# Arm_controller.net
KiCad netlist of a schematic drawn in EAGLE
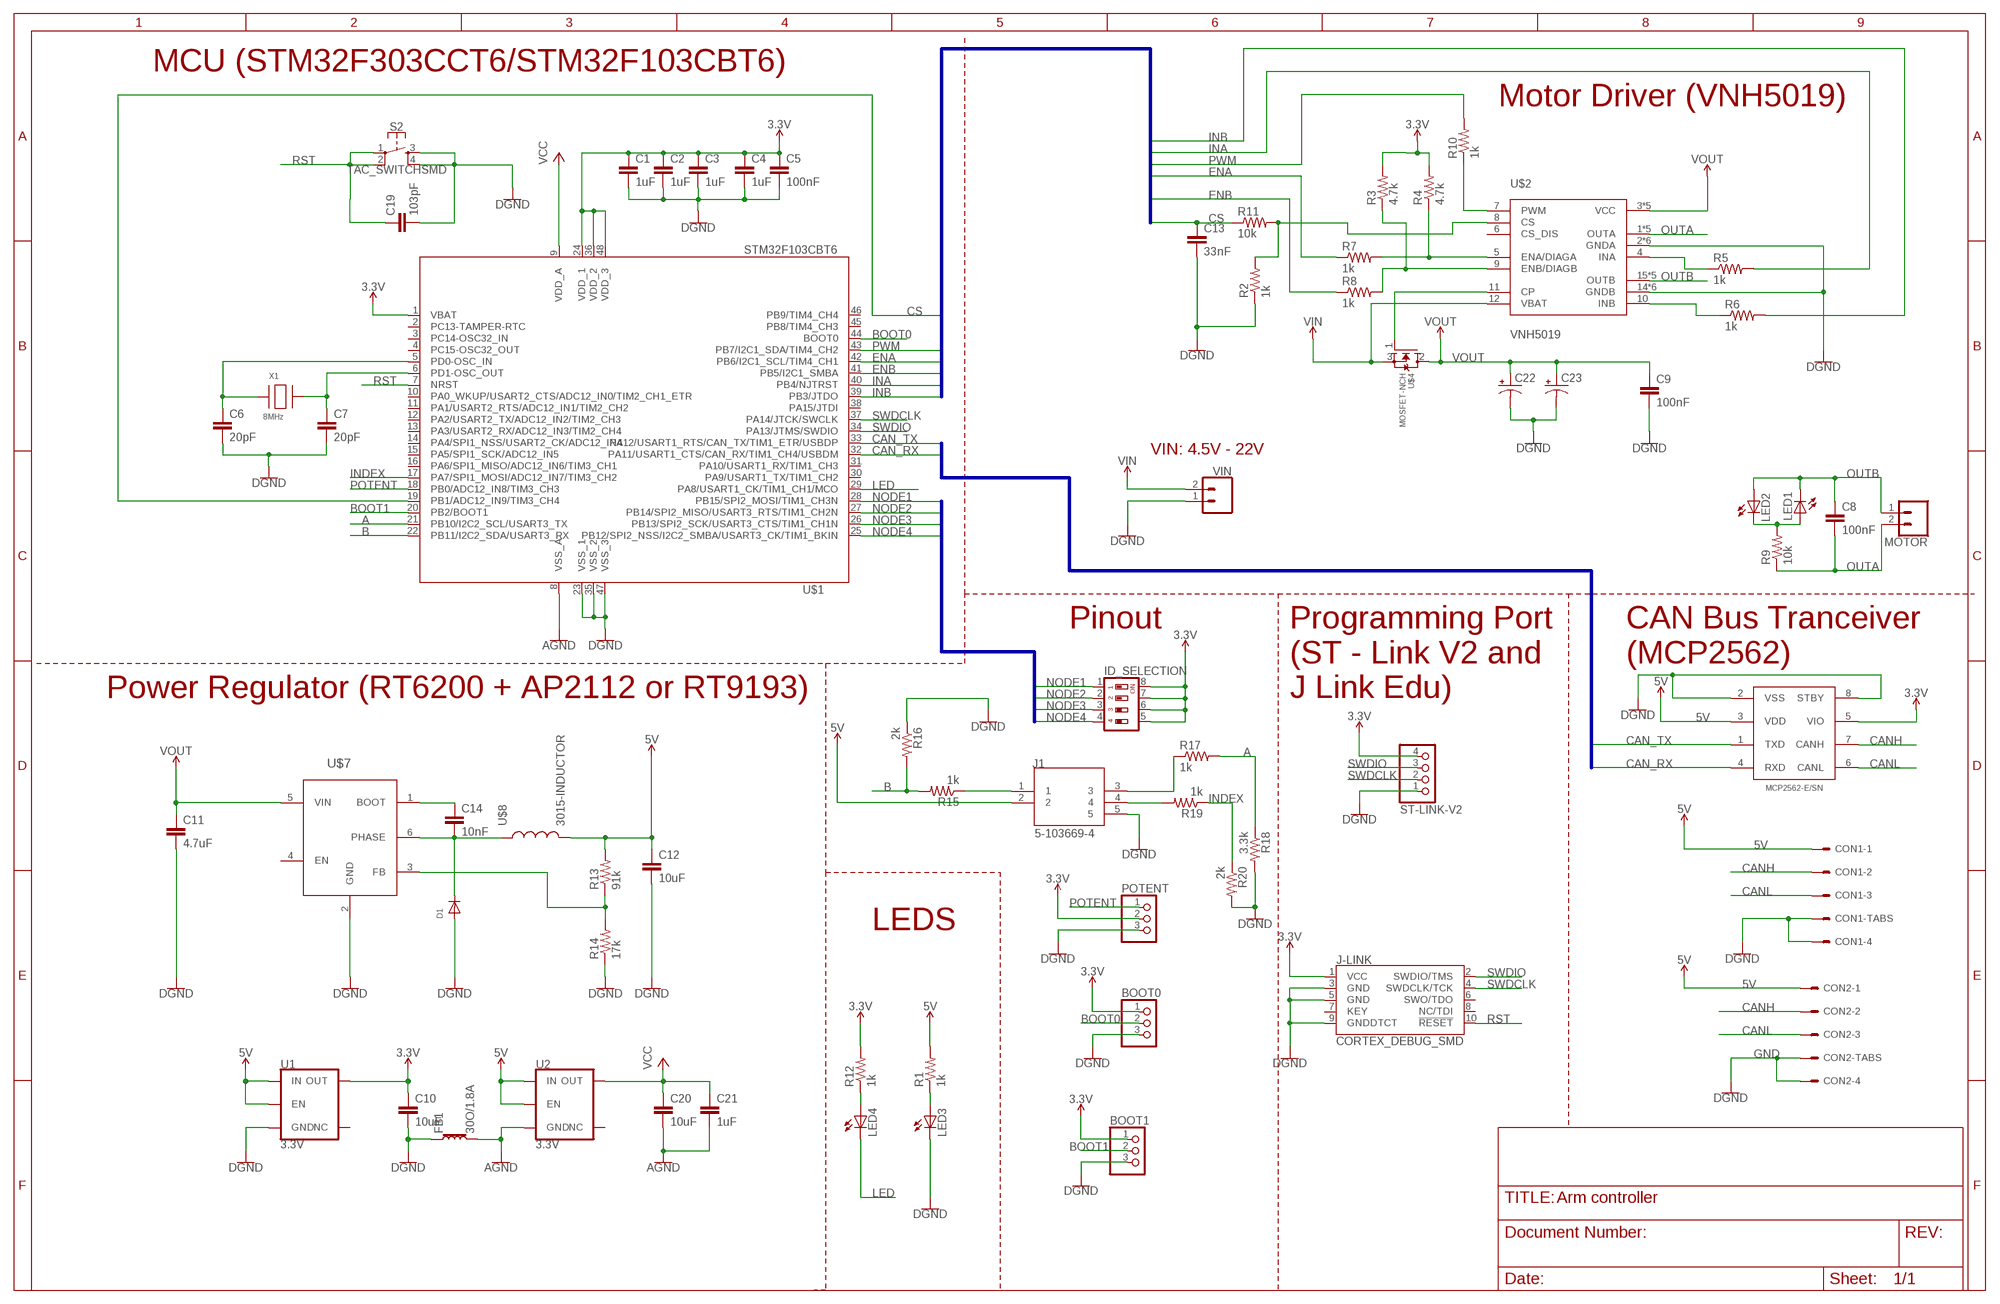
[diagram p0: schematic, sheet 1]

(export (version "E")
  (design (tool "Eeschema 10.0.6"))
  (components
    (comp (ref "BOOT0")
      (value "PINHD-1X3")
      (footprint "eagle-import:1X03")
      (libsource (lib "eagle-import") (part "PINHD-1X3"))
    )
    (comp (ref "BOOT1")
      (value "PINHD-1X3")
      (footprint "eagle-import:1X03")
      (libsource (lib "eagle-import") (part "PINHD-1X3"))
    )
    (comp (ref "C1")
      (value "1uF")
      (footprint "eagle-import:C0805")
      (libsource (lib "eagle-import") (part "C-EUC0805"))
    )
    (comp (ref "C2")
      (value "1uF")
      (footprint "eagle-import:C0805")
      (libsource (lib "eagle-import") (part "C-EUC0805"))
    )
    (comp (ref "C3")
      (value "1uF")
      (footprint "eagle-import:C0805")
      (libsource (lib "eagle-import") (part "C-EUC0805"))
    )
    (comp (ref "C4")
      (value "1uF")
      (footprint "eagle-import:C0805")
      (libsource (lib "eagle-import") (part "C-EUC0805"))
    )
    (comp (ref "C5")
      (value "100nF")
      (footprint "eagle-import:C0805")
      (libsource (lib "eagle-import") (part "C-EUC0805"))
    )
    (comp (ref "C6")
      (value "20pF")
      (footprint "eagle-import:C0805")
      (libsource (lib "eagle-import") (part "C-EUC0805"))
    )
    (comp (ref "C7")
      (value "20pF")
      (footprint "eagle-import:C0805")
      (libsource (lib "eagle-import") (part "C-EUC0805"))
    )
    (comp (ref "C8")
      (value "100nF")
      (footprint "eagle-import:C1206")
      (libsource (lib "eagle-import") (part "resistor_348_C-EUC1206"))
    )
    (comp (ref "C9")
      (value "100nF")
      (footprint "eagle-import:C0805")
      (libsource (lib "eagle-import") (part "C-EUC0805"))
    )
    (comp (ref "C10")
      (value "10uF")
      (footprint "eagle-import:C1206")
      (libsource (lib "eagle-import") (part "resistor_348_C-EUC1206"))
    )
    (comp (ref "C11")
      (value "4.7uF")
      (footprint "eagle-import:C0805")
      (libsource (lib "eagle-import") (part "C-EUC0805"))
    )
    (comp (ref "C12")
      (value "10uF")
      (footprint "eagle-import:C0805")
      (libsource (lib "eagle-import") (part "C-EUC0805"))
    )
    (comp (ref "C13")
      (value "33nF")
      (footprint "eagle-import:C0805")
      (libsource (lib "eagle-import") (part "C-EUC0805"))
    )
    (comp (ref "C14")
      (value "10nF")
      (footprint "eagle-import:C0805")
      (libsource (lib "eagle-import") (part "C-EUC0805"))
    )
    (comp (ref "C19")
      (value "103pF")
      (footprint "eagle-import:C0805")
      (libsource (lib "eagle-import") (part "C-EUC0805"))
    )
    (comp (ref "C20")
      (value "10uF")
      (footprint "eagle-import:C1206")
      (libsource (lib "eagle-import") (part "resistor_348_C-EUC1206"))
    )
    (comp (ref "C21")
      (value "1uF")
      (footprint "eagle-import:C0805")
      (libsource (lib "eagle-import") (part "C-EUC0805"))
    )
    (comp (ref "C22")
      (value "CPOL-USCT7343")
      (footprint "eagle-import:CT7343")
      (libsource (lib "eagle-import") (part "CPOL-USCT7343"))
    )
    (comp (ref "C23")
      (value "CPOL-USCT7343")
      (footprint "eagle-import:CT7343")
      (libsource (lib "eagle-import") (part "CPOL-USCT7343"))
    )
    (comp (ref "CON1")
      (value "SM04B-GHS-TB")
      (footprint "eagle-import:SM04B-GHS-TB")
      (libsource (lib "eagle-import") (part "SM04B-GHS-TB"))
    )
    (comp (ref "CON2")
      (value "SM04B-GHS-TB")
      (footprint "eagle-import:SM04B-GHS-TB")
      (libsource (lib "eagle-import") (part "SM04B-GHS-TB"))
    )
    (comp (ref "D1")
      (value "DIODESOD-123")
      (footprint "eagle-import:SOD-123")
      (libsource (lib "eagle-import") (part "DIODESOD-123"))
    )
    (comp (ref "FB1")
      (value "30O/1.8A")
      (footprint "eagle-import:0603")
      (libsource (lib "eagle-import") (part "FERRITE_BEAD-0603"))
    )
    (comp (ref "ID_SELECTION")
      (value "SMS-004")
      (footprint "eagle-import:SMS-004")
      (libsource (lib "eagle-import") (part "SMS-004"))
    )
    (comp (ref "J-LINK")
      (value "CORTEX_DEBUG_SMD")
      (footprint "eagle-import:SAMTECH_FTSH-105-01")
      (libsource (lib "eagle-import") (part "CORTEX_DEBUG_SMD"))
    )
    (comp (ref "J1")
      (value "5-103669-4")
      (footprint "eagle-import:TE_5-103669-4")
      (fields (field (name "MF") "TE Connectivity"))
      (libsource (lib "eagle-import") (part "5-103669-4"))
    )
    (comp (ref "LED1")
      (value "LEDCHIPLED_0805")
      (footprint "eagle-import:CHIPLED_0805")
      (libsource (lib "eagle-import") (part "LEDCHIPLED_0805"))
    )
    (comp (ref "LED2")
      (value "LEDCHIPLED_0805")
      (footprint "eagle-import:CHIPLED_0805")
      (libsource (lib "eagle-import") (part "LEDCHIPLED_0805"))
    )
    (comp (ref "LED3")
      (value "LEDCHIPLED_0805")
      (footprint "eagle-import:CHIPLED_0805")
      (libsource (lib "eagle-import") (part "LEDCHIPLED_0805"))
    )
    (comp (ref "LED4")
      (value "LEDCHIPLED_0805")
      (footprint "eagle-import:CHIPLED_0805")
      (libsource (lib "eagle-import") (part "LEDCHIPLED_0805"))
    )
    (comp (ref "MOTOR")
      (value "CONN_025MM")
      (footprint "eagle-import:SCREWTERMINAL-5MM-2")
      (libsource (lib "eagle-import") (part "CONN_025MM"))
    )
    (comp (ref "POTENT")
      (value "PINHD-1X3")
      (footprint "eagle-import:1X03")
      (libsource (lib "eagle-import") (part "PINHD-1X3"))
    )
    (comp (ref "R1")
      (value "1k")
      (footprint "eagle-import:R0805")
      (libsource (lib "eagle-import") (part "R-US_R0805"))
    )
    (comp (ref "R2")
      (value "1k")
      (footprint "eagle-import:R0805")
      (libsource (lib "eagle-import") (part "R-US_R0805"))
    )
    (comp (ref "R3")
      (value "4.7k")
      (footprint "eagle-import:R0805")
      (libsource (lib "eagle-import") (part "R-US_R0805"))
    )
    (comp (ref "R4")
      (value "4.7k")
      (footprint "eagle-import:R0805")
      (libsource (lib "eagle-import") (part "R-US_R0805"))
    )
    (comp (ref "R5")
      (value "1k")
      (footprint "eagle-import:R0805")
      (libsource (lib "eagle-import") (part "R-US_R0805"))
    )
    (comp (ref "R6")
      (value "1k")
      (footprint "eagle-import:R0805")
      (libsource (lib "eagle-import") (part "R-US_R0805"))
    )
    (comp (ref "R7")
      (value "1k")
      (footprint "eagle-import:R0805")
      (libsource (lib "eagle-import") (part "R-US_R0805"))
    )
    (comp (ref "R8")
      (value "1k")
      (footprint "eagle-import:R0805")
      (libsource (lib "eagle-import") (part "R-US_R0805"))
    )
    (comp (ref "R9")
      (value "10k")
      (footprint "eagle-import:R0805")
      (libsource (lib "eagle-import") (part "R-US_R0805"))
    )
    (comp (ref "R10")
      (value "1k")
      (footprint "eagle-import:R0805")
      (libsource (lib "eagle-import") (part "R-US_R0805"))
    )
    (comp (ref "R11")
      (value "10k")
      (footprint "eagle-import:R0805")
      (libsource (lib "eagle-import") (part "R-US_R0805"))
    )
    (comp (ref "R12")
      (value "1k")
      (footprint "eagle-import:R0805")
      (libsource (lib "eagle-import") (part "R-US_R0805"))
    )
    (comp (ref "R13")
      (value "91k")
      (footprint "eagle-import:R0805")
      (libsource (lib "eagle-import") (part "R-US_R0805"))
    )
    (comp (ref "R14")
      (value "17k")
      (footprint "eagle-import:R0805")
      (libsource (lib "eagle-import") (part "R-US_R0805"))
    )
    (comp (ref "R15")
      (value "1k")
      (footprint "eagle-import:R0805")
      (libsource (lib "eagle-import") (part "R-US_R0805"))
    )
    (comp (ref "R16")
      (value "2k")
      (footprint "eagle-import:R0805")
      (libsource (lib "eagle-import") (part "R-US_R0805"))
    )
    (comp (ref "R17")
      (value "1k")
      (footprint "eagle-import:R0805")
      (libsource (lib "eagle-import") (part "R-US_R0805"))
    )
    (comp (ref "R18")
      (value "3.3k")
      (footprint "eagle-import:R0805")
      (libsource (lib "eagle-import") (part "R-US_R0805"))
    )
    (comp (ref "R19")
      (value "1k")
      (footprint "eagle-import:R0805")
      (libsource (lib "eagle-import") (part "R-US_R0805"))
    )
    (comp (ref "R20")
      (value "2k")
      (footprint "eagle-import:R0805")
      (libsource (lib "eagle-import") (part "R-US_R0805"))
    )
    (comp (ref "S2")
      (value "TAC_SWITCHSMD")
      (footprint "eagle-import:TACTILE_SWITCH_SMD_5.2MM")
      (libsource (lib "eagle-import") (part "MOMENTARY-SWITCH-SPST-2-SMD-5.2MM"))
    )
    (comp (ref "ST-LINK-V2")
      (value "PINHD-1X4")
      (footprint "eagle-import:1X04")
      (libsource (lib "eagle-import") (part "PINHD-1X4"))
    )
    (comp (ref "U$1")
      (value "STM32F103CBT6")
      (footprint "eagle-import:STM32_LQFP48")
      (libsource (lib "eagle-import") (part "STM32F103CBT6"))
    )
    (comp (ref "U$2")
      (value "VNH5019")
      (footprint "eagle-import:MULTIPOWERSO-30")
      (libsource (lib "eagle-import") (part "VNH5019"))
    )
    (comp (ref "U$3")
      (value "MCP2562-E/SN")
      (footprint "eagle-import:SOIC8")
      (libsource (lib "eagle-import") (part "MCP2562-E/SN"))
    )
    (comp (ref "U$4")
      (value "MOSFET-NCH")
      (footprint "eagle-import:TO252-3")
      (libsource (lib "eagle-import") (part "MOSFET-NCH"))
    )
    (comp (ref "U$7")
      (value "RT6200")
      (footprint "eagle-import:TSOT23-6")
      (libsource (lib "eagle-import") (part "RT6200"))
    )
    (comp (ref "U$8")
      (value "3015-INDUCTOR")
      (footprint "eagle-import:3015")
      (libsource (lib "eagle-import") (part "3015-INDUCTOR"))
    )
    (comp (ref "U1")
      (value "3.3V")
      (footprint "eagle-import:SOT23-5")
      (libsource (lib "eagle-import") (part "V_REG_AP2112K-3.3V"))
    )
    (comp (ref "U2")
      (value "3.3V")
      (footprint "eagle-import:SOT23-5")
      (libsource (lib "eagle-import") (part "V_REG_AP2112K-3.3V"))
    )
    (comp (ref "VIN")
      (value "CONN_025MM")
      (footprint "eagle-import:SCREWTERMINAL-5MM-2")
      (libsource (lib "eagle-import") (part "CONN_025MM"))
    )
    (comp (ref "X1")
      (value "8MHz")
      (footprint "eagle-import:NX5032")
      (libsource (lib "eagle-import") (part "XTALNX5032"))
    )
  )
  (nets
    (net (code "1") (name "/A") (class "Default")
      (node (ref "R17") (pin "2") (pinfunction "2_2") (pintype "passive"))
      (node (ref "R18") (pin "1") (pinfunction "1_1") (pintype "passive"))
      (node (ref "U$1") (pin "21") (pinfunction "PB10/I2C2_SCL/USART3_TX_21") (pintype "input"))
    )
    (net (code "2") (name "/B") (class "Default")
      (node (ref "R15") (pin "2") (pinfunction "2_2") (pintype "passive"))
      (node (ref "R16") (pin "2") (pinfunction "2_2") (pintype "passive"))
      (node (ref "U$1") (pin "22") (pinfunction "PB11/I2C2_SDA/USART3_RX_22") (pintype "input"))
    )
    (net (code "3") (name "/BOOT0") (class "Default")
      (node (ref "BOOT0") (pin "2") (pinfunction "2_2") (pintype "passive"))
      (node (ref "U$1") (pin "44") (pinfunction "BOOT0_44") (pintype "input"))
    )
    (net (code "4") (name "/BOOT1") (class "Default")
      (node (ref "BOOT1") (pin "2") (pinfunction "2_2") (pintype "passive"))
      (node (ref "U$1") (pin "20") (pinfunction "PB2/BOOT1_20") (pintype "bidirectional"))
    )
    (net (code "5") (name "/CANH") (class "Default")
      (node (ref "CON1") (pin "P$2") (pinfunction "S_P$2") (pintype "passive"))
      (node (ref "CON2") (pin "P$2") (pinfunction "S_P$2") (pintype "passive"))
      (node (ref "U$3") (pin "7") (pinfunction "CANH_7") (pintype "bidirectional"))
    )
    (net (code "6") (name "/CANL") (class "Default")
      (node (ref "CON1") (pin "P$3") (pinfunction "S_P$3") (pintype "passive"))
      (node (ref "CON2") (pin "P$3") (pinfunction "S_P$3") (pintype "passive"))
      (node (ref "U$3") (pin "6") (pinfunction "CANL_6") (pintype "bidirectional"))
    )
    (net (code "7") (name "/CAN_RX") (class "Default")
      (node (ref "U$1") (pin "32") (pinfunction "PA11/USART1_CTS/CAN_RX/TIM1_CH4/USBDM_32") (pintype "bidirectional"))
      (node (ref "U$3") (pin "4") (pinfunction "RXD_4") (pintype "bidirectional"))
    )
    (net (code "8") (name "/CAN_TX") (class "Default")
      (node (ref "U$1") (pin "33") (pinfunction "PA12/USART1_RTS/CAN_TX/TIM1_ETR/USBDP_33") (pintype "bidirectional"))
      (node (ref "U$3") (pin "1") (pinfunction "TXD_1") (pintype "bidirectional"))
    )
    (net (code "9") (name "/CS") (class "Default")
      (node (ref "C13") (pin "1") (pinfunction "1_1") (pintype "passive"))
      (node (ref "R11") (pin "1") (pinfunction "1_1") (pintype "passive"))
      (node (ref "U$1") (pin "19") (pinfunction "PB1/ADC12_IN9/TIM3_CH4_19") (pintype "bidirectional"))
    )
    (net (code "10") (name "/ENA") (class "Default")
      (node (ref "R7") (pin "1") (pinfunction "1_1") (pintype "passive"))
      (node (ref "U$1") (pin "42") (pinfunction "PB6/I2C1_SCL/TIM4_CH1_42") (pintype "input"))
    )
    (net (code "11") (name "/ENB") (class "Default")
      (node (ref "R8") (pin "1") (pinfunction "1_1") (pintype "passive"))
      (node (ref "U$1") (pin "41") (pinfunction "PB5/I2C1_SMBA_41") (pintype "input"))
    )
    (net (code "12") (name "/INA") (class "Default")
      (node (ref "R5") (pin "2") (pinfunction "2_2") (pintype "passive"))
      (node (ref "U$1") (pin "40") (pinfunction "PB4/NJTRST_40") (pintype "bidirectional"))
    )
    (net (code "13") (name "/INB") (class "Default")
      (node (ref "R6") (pin "2") (pinfunction "2_2") (pintype "passive"))
      (node (ref "U$1") (pin "39") (pinfunction "PB3/JTDO_39") (pintype "bidirectional"))
    )
    (net (code "14") (name "/INDEX") (class "Default")
      (node (ref "R19") (pin "1") (pinfunction "1_1") (pintype "passive"))
      (node (ref "R20") (pin "1") (pinfunction "1_1") (pintype "passive"))
      (node (ref "U$1") (pin "17") (pinfunction "PA7/SPI1_MOSI/ADC12_IN7/TIM3_CH2_17") (pintype "bidirectional"))
    )
    (net (code "15") (name "/LED") (class "Default")
      (node (ref "LED4") (pin "C") (pinfunction "C_C") (pintype "passive"))
      (node (ref "U$1") (pin "29") (pinfunction "PA8/USART1_CK/TIM1_CH1/MCO_29") (pintype "bidirectional"))
    )
    (net (code "16") (name "/NODE1") (class "Default")
      (node (ref "ID_SELECTION") (pin "1") (pinfunction "1_1") (pintype "passive"))
      (node (ref "U$1") (pin "28") (pinfunction "PB15/SPI2_MOSI/TIM1_CH3N_28") (pintype "input"))
    )
    (net (code "17") (name "/NODE2") (class "Default")
      (node (ref "ID_SELECTION") (pin "2") (pinfunction "2_2") (pintype "passive"))
      (node (ref "U$1") (pin "27") (pinfunction "PB14/SPI2_MISO/USART3_RTS/TIM1_CH2N_27") (pintype "input"))
    )
    (net (code "18") (name "/NODE3") (class "Default")
      (node (ref "ID_SELECTION") (pin "3") (pinfunction "3_3") (pintype "passive"))
      (node (ref "U$1") (pin "26") (pinfunction "PB13/SPI2_SCK/USART3_CTS/TIM1_CH1N_26") (pintype "input"))
    )
    (net (code "19") (name "/NODE4") (class "Default")
      (node (ref "ID_SELECTION") (pin "4") (pinfunction "4_4") (pintype "passive"))
      (node (ref "U$1") (pin "25") (pinfunction "PB12/SPI2_NSS/I2C2_SMBA/USART3_CK/TIM1_BKIN_25") (pintype "input"))
    )
    (net (code "20") (name "/OUTA") (class "Default")
      (node (ref "C8") (pin "2") (pinfunction "2_2") (pintype "passive"))
      (node (ref "MOTOR") (pin "2") (pinfunction "2_2") (pintype "passive"))
      (node (ref "R9") (pin "1") (pinfunction "1_1") (pintype "passive"))
      (node (ref "U$2") (pin "1") (pinfunction "OUTA_1") (pintype "bidirectional"))
      (node (ref "U$2") (pin "25") (pinfunction "OUTA_25") (pintype "bidirectional"))
      (node (ref "U$2") (pin "30") (pinfunction "OUTA_30") (pintype "bidirectional"))
      (node (ref "U$2") (pin "OUTA") (pinfunction "OUTA_OUTA") (pintype "bidirectional"))
      (node (ref "U$2") (pin "OUTA@1") (pinfunction "OUTA_OUTA@1") (pintype "bidirectional"))
    )
    (net (code "21") (name "/OUTB") (class "Default")
      (node (ref "C8") (pin "1") (pinfunction "1_1") (pintype "passive"))
      (node (ref "LED1") (pin "C") (pinfunction "C_C") (pintype "passive"))
      (node (ref "LED2") (pin "A") (pinfunction "A_A") (pintype "passive"))
      (node (ref "MOTOR") (pin "1") (pinfunction "1_1") (pintype "passive"))
      (node (ref "U$2") (pin "15") (pinfunction "OUTB_15") (pintype "bidirectional"))
      (node (ref "U$2") (pin "16") (pinfunction "OUTB_16") (pintype "bidirectional"))
      (node (ref "U$2") (pin "21") (pinfunction "OUTB_21") (pintype "bidirectional"))
      (node (ref "U$2") (pin "OUTB") (pinfunction "OUTB_OUTB") (pintype "bidirectional"))
      (node (ref "U$2") (pin "OUTB@1") (pinfunction "OUTB_OUTB@1") (pintype "bidirectional"))
    )
    (net (code "22") (name "/POTENT") (class "Default")
      (node (ref "POTENT") (pin "1") (pinfunction "1_1") (pintype "passive"))
      (node (ref "U$1") (pin "18") (pinfunction "PB0/ADC12_IN8/TIM3_CH3_18") (pintype "bidirectional"))
    )
    (net (code "23") (name "/PWM") (class "Default")
      (node (ref "R10") (pin "2") (pinfunction "2_2") (pintype "passive"))
      (node (ref "U$1") (pin "43") (pinfunction "PB7/I2C1_SDA/TIM4_CH2_43") (pintype "bidirectional"))
    )
    (net (code "24") (name "/RST") (class "Default")
      (node (ref "C19") (pin "1") (pinfunction "1_1") (pintype "passive"))
      (node (ref "J-LINK") (pin "10") (pinfunction "~{RESET}_10") (pintype "bidirectional"))
      (node (ref "S2") (pin "1") (pinfunction "1_1") (pintype "passive"))
      (node (ref "S2") (pin "2") (pinfunction "2_2") (pintype "passive"))
      (node (ref "U$1") (pin "7") (pinfunction "NRST_7") (pintype "input"))
    )
    (net (code "25") (name "/SWDCLK") (class "Default")
      (node (ref "J-LINK") (pin "4") (pinfunction "SWDCLK/TCK_4") (pintype "bidirectional"))
      (node (ref "ST-LINK-V2") (pin "2") (pinfunction "2_2") (pintype "passive"))
      (node (ref "U$1") (pin "37") (pinfunction "PA14/JTCK/SWCLK_37") (pintype "bidirectional"))
    )
    (net (code "26") (name "/SWDIO") (class "Default")
      (node (ref "J-LINK") (pin "2") (pinfunction "SWDIO/TMS_2") (pintype "bidirectional"))
      (node (ref "ST-LINK-V2") (pin "3") (pinfunction "3_3") (pintype "passive"))
      (node (ref "U$1") (pin "34") (pinfunction "PA13/JTMS/SWDIO_34") (pintype "bidirectional"))
    )
    (net (code "27") (name "3.3V") (class "Default")
      (node (ref "BOOT0") (pin "1") (pinfunction "1_1") (pintype "passive"))
      (node (ref "BOOT1") (pin "1") (pinfunction "1_1") (pintype "passive"))
      (node (ref "C1") (pin "1") (pinfunction "1_1") (pintype "passive"))
      (node (ref "C10") (pin "1") (pinfunction "1_1") (pintype "passive"))
      (node (ref "C2") (pin "1") (pinfunction "1_1") (pintype "passive"))
      (node (ref "C3") (pin "1") (pinfunction "1_1") (pintype "passive"))
      (node (ref "C4") (pin "1") (pinfunction "1_1") (pintype "passive"))
      (node (ref "C5") (pin "1") (pinfunction "1_1") (pintype "passive"))
      (node (ref "ID_SELECTION") (pin "5") (pinfunction "5_5") (pintype "passive"))
      (node (ref "ID_SELECTION") (pin "6") (pinfunction "6_6") (pintype "passive"))
      (node (ref "ID_SELECTION") (pin "7") (pinfunction "7_7") (pintype "passive"))
      (node (ref "ID_SELECTION") (pin "8") (pinfunction "8_8") (pintype "passive"))
      (node (ref "J-LINK") (pin "1") (pinfunction "VCC_1") (pintype "bidirectional"))
      (node (ref "POTENT") (pin "2") (pinfunction "2_2") (pintype "passive"))
      (node (ref "R12") (pin "2") (pinfunction "2_2") (pintype "passive"))
      (node (ref "R3") (pin "2") (pinfunction "2_2") (pintype "passive"))
      (node (ref "R4") (pin "2") (pinfunction "2_2") (pintype "passive"))
      (node (ref "ST-LINK-V2") (pin "4") (pinfunction "4_4") (pintype "passive"))
      (node (ref "U$1") (pin "1") (pinfunction "VBAT_1") (pintype "power_in"))
      (node (ref "U$1") (pin "24") (pinfunction "VDD_1_24") (pintype "power_in"))
      (node (ref "U$1") (pin "36") (pinfunction "VDD_2_36") (pintype "power_in"))
      (node (ref "U$1") (pin "48") (pinfunction "VDD_3_48") (pintype "power_in"))
      (node (ref "U$3") (pin "5") (pinfunction "VIO_5") (pintype "bidirectional"))
      (node (ref "U1") (pin "5") (pinfunction "OUT_5") (pintype "passive"))
    )
    (net (code "28") (name "5V") (class "Default")
      (node (ref "C12") (pin "1") (pinfunction "1_1") (pintype "passive"))
      (node (ref "CON1") (pin "P$1") (pinfunction "S_P$1") (pintype "passive"))
      (node (ref "CON2") (pin "P$1") (pinfunction "S_P$1") (pintype "passive"))
      (node (ref "J1") (pin "2") (pinfunction "2_2") (pintype "passive"))
      (node (ref "R1") (pin "2") (pinfunction "2_2") (pintype "passive"))
      (node (ref "R13") (pin "2") (pinfunction "2_2") (pintype "passive"))
      (node (ref "U$3") (pin "3") (pinfunction "VDD_3") (pintype "bidirectional"))
      (node (ref "U$8") (pin "2") (pinfunction "2_2") (pintype "passive"))
      (node (ref "U1") (pin "1") (pinfunction "IN_1") (pintype "input"))
      (node (ref "U1") (pin "3") (pinfunction "EN_3") (pintype "input"))
      (node (ref "U2") (pin "1") (pinfunction "IN_1") (pintype "input"))
      (node (ref "U2") (pin "3") (pinfunction "EN_3") (pintype "input"))
    )
    (net (code "29") (name "AGND") (class "Default")
      (node (ref "C20") (pin "2") (pinfunction "2_2") (pintype "passive"))
      (node (ref "C21") (pin "2") (pinfunction "2_2") (pintype "passive"))
      (node (ref "FB1") (pin "2") (pinfunction "2_2") (pintype "passive"))
      (node (ref "U$1") (pin "8") (pinfunction "VSS_A_8") (pintype "power_in"))
      (node (ref "U2") (pin "2") (pinfunction "GND_2") (pintype "input"))
    )
    (net (code "30") (name "DGND") (class "Default")
      (node (ref "BOOT0") (pin "3") (pinfunction "3_3") (pintype "passive"))
      (node (ref "BOOT1") (pin "3") (pinfunction "3_3") (pintype "passive"))
      (node (ref "C1") (pin "2") (pinfunction "2_2") (pintype "passive"))
      (node (ref "C10") (pin "2") (pinfunction "2_2") (pintype "passive"))
      (node (ref "C11") (pin "2") (pinfunction "2_2") (pintype "passive"))
      (node (ref "C12") (pin "2") (pinfunction "2_2") (pintype "passive"))
      (node (ref "C13") (pin "2") (pinfunction "2_2") (pintype "passive"))
      (node (ref "C19") (pin "2") (pinfunction "2_2") (pintype "passive"))
      (node (ref "C2") (pin "2") (pinfunction "2_2") (pintype "passive"))
      (node (ref "C22") (pin "-") (pinfunction "-_-") (pintype "passive"))
      (node (ref "C23") (pin "-") (pinfunction "-_-") (pintype "passive"))
      (node (ref "C3") (pin "2") (pinfunction "2_2") (pintype "passive"))
      (node (ref "C4") (pin "2") (pinfunction "2_2") (pintype "passive"))
      (node (ref "C5") (pin "2") (pinfunction "2_2") (pintype "passive"))
      (node (ref "C6") (pin "2") (pinfunction "2_2") (pintype "passive"))
      (node (ref "C7") (pin "2") (pinfunction "2_2") (pintype "passive"))
      (node (ref "C9") (pin "2") (pinfunction "2_2") (pintype "passive"))
      (node (ref "CON1") (pin "P$4") (pinfunction "S_P$4") (pintype "passive"))
      (node (ref "CON1") (pin "P$5") (pinfunction "S_P$5") (pintype "passive"))
      (node (ref "CON1") (pin "P$6") (pinfunction "S_P$6") (pintype "passive"))
      (node (ref "CON2") (pin "P$4") (pinfunction "S_P$4") (pintype "passive"))
      (node (ref "CON2") (pin "P$5") (pinfunction "S_P$5") (pintype "passive"))
      (node (ref "CON2") (pin "P$6") (pinfunction "S_P$6") (pintype "passive"))
      (node (ref "D1") (pin "A") (pinfunction "A_A") (pintype "passive"))
      (node (ref "FB1") (pin "1") (pinfunction "1_1") (pintype "passive"))
      (node (ref "J-LINK") (pin "3") (pinfunction "GND_3") (pintype "bidirectional"))
      (node (ref "J-LINK") (pin "5") (pinfunction "GND_5") (pintype "bidirectional"))
      (node (ref "J-LINK") (pin "9") (pinfunction "GNDDTCT_9") (pintype "bidirectional"))
      (node (ref "J1") (pin "5") (pinfunction "5_5") (pintype "passive"))
      (node (ref "LED3") (pin "C") (pinfunction "C_C") (pintype "passive"))
      (node (ref "POTENT") (pin "3") (pinfunction "3_3") (pintype "passive"))
      (node (ref "R14") (pin "1") (pinfunction "1_1") (pintype "passive"))
      (node (ref "R16") (pin "1") (pinfunction "1_1") (pintype "passive"))
      (node (ref "R18") (pin "2") (pinfunction "2_2") (pintype "passive"))
      (node (ref "R2") (pin "1") (pinfunction "1_1") (pintype "passive"))
      (node (ref "R20") (pin "2") (pinfunction "2_2") (pintype "passive"))
      (node (ref "S2") (pin "3") (pinfunction "3_3") (pintype "passive"))
      (node (ref "S2") (pin "4") (pinfunction "4_4") (pintype "passive"))
      (node (ref "ST-LINK-V2") (pin "1") (pinfunction "1_1") (pintype "passive"))
      (node (ref "U$1") (pin "23") (pinfunction "VSS_1_23") (pintype "power_in"))
      (node (ref "U$1") (pin "35") (pinfunction "VSS_2_35") (pintype "power_in"))
      (node (ref "U$1") (pin "47") (pinfunction "VSS_3_47") (pintype "power_in"))
      (node (ref "U$2") (pin "14") (pinfunction "GNDB_14") (pintype "bidirectional"))
      (node (ref "U$2") (pin "17") (pinfunction "GNDB_17") (pintype "bidirectional"))
      (node (ref "U$2") (pin "18") (pinfunction "GNDB_18") (pintype "bidirectional"))
      (node (ref "U$2") (pin "19") (pinfunction "GNDB_19") (pintype "bidirectional"))
      (node (ref "U$2") (pin "2") (pinfunction "GNDA_2") (pintype "bidirectional"))
      (node (ref "U$2") (pin "20") (pinfunction "GNDB_20") (pintype "bidirectional"))
      (node (ref "U$2") (pin "22") (pinfunction "GNDA_22") (pintype "bidirectional"))
      (node (ref "U$2") (pin "24") (pinfunction "GNDB_24") (pintype "bidirectional"))
      (node (ref "U$2") (pin "26") (pinfunction "GNDA_26") (pintype "bidirectional"))
      (node (ref "U$2") (pin "27") (pinfunction "GNDA_27") (pintype "bidirectional"))
      (node (ref "U$2") (pin "28") (pinfunction "GNDA_28") (pintype "bidirectional"))
      (node (ref "U$2") (pin "29") (pinfunction "GNDA_29") (pintype "bidirectional"))
      (node (ref "U$3") (pin "2") (pinfunction "VSS_2") (pintype "bidirectional"))
      (node (ref "U$3") (pin "8") (pinfunction "STBY_8") (pintype "bidirectional"))
      (node (ref "U$7") (pin "2") (pinfunction "GND_2") (pintype "power_in"))
      (node (ref "U1") (pin "2") (pinfunction "GND_2") (pintype "input"))
      (node (ref "VIN") (pin "1") (pinfunction "1_1") (pintype "passive"))
    )
    (net (code "31") (name "Net-(J1-Pad1)") (class "Default")
      (node (ref "J1") (pin "1") (pinfunction "1_1") (pintype "passive"))
      (node (ref "R15") (pin "1") (pinfunction "1_1") (pintype "passive"))
    )
    (net (code "32") (name "Net-(J1-Pad3)") (class "Default")
      (node (ref "J1") (pin "3") (pinfunction "3_3") (pintype "passive"))
      (node (ref "R17") (pin "1") (pinfunction "1_1") (pintype "passive"))
    )
    (net (code "33") (name "Net-(J1-Pad4)") (class "Default")
      (node (ref "J1") (pin "4") (pinfunction "4_4") (pintype "passive"))
      (node (ref "R19") (pin "2") (pinfunction "2_2") (pintype "passive"))
    )
    (net (code "34") (name "Net-(LED1-PadA)") (class "Default")
      (node (ref "LED1") (pin "A") (pinfunction "A_A") (pintype "passive"))
      (node (ref "LED2") (pin "C") (pinfunction "C_C") (pintype "passive"))
      (node (ref "R9") (pin "2") (pinfunction "2_2") (pintype "passive"))
    )
    (net (code "35") (name "Net-(LED3-PadA)") (class "Default")
      (node (ref "LED3") (pin "A") (pinfunction "A_A") (pintype "passive"))
      (node (ref "R1") (pin "1") (pinfunction "1_1") (pintype "passive"))
    )
    (net (code "36") (name "Net-(LED4-PadA)") (class "Default")
      (node (ref "LED4") (pin "A") (pinfunction "A_A") (pintype "passive"))
      (node (ref "R12") (pin "1") (pinfunction "1_1") (pintype "passive"))
    )
    (net (code "37") (name "Net-(U$1-PD0-OSC_IN)") (class "Default")
      (node (ref "C6") (pin "1") (pinfunction "1_1") (pintype "passive"))
      (node (ref "U$1") (pin "5") (pinfunction "PD0-OSC_IN_5") (pintype "input"))
      (node (ref "X1") (pin "P$1") (pinfunction "P$1_P$1") (pintype "bidirectional"))
    )
    (net (code "38") (name "Net-(U$1-PD1-OSC_OUT)") (class "Default")
      (node (ref "C7") (pin "1") (pinfunction "1_1") (pintype "passive"))
      (node (ref "U$1") (pin "6") (pinfunction "PD1-OSC_OUT_6") (pintype "input"))
      (node (ref "X1") (pin "P$2") (pinfunction "P$2_P$2") (pintype "bidirectional"))
    )
    (net (code "39") (name "Net-(U$2-CP)") (class "Default")
      (node (ref "U$2") (pin "11") (pinfunction "CP_11") (pintype "bidirectional"))
      (node (ref "U$4") (pin "1") (pinfunction "G_1") (pintype "bidirectional"))
    )
    (net (code "40") (name "Net-(U$2-CS)") (class "Default")
      (node (ref "R11") (pin "2") (pinfunction "2_2") (pintype "passive"))
      (node (ref "R2") (pin "2") (pinfunction "2_2") (pintype "passive"))
      (node (ref "U$2") (pin "8") (pinfunction "CS_8") (pintype "bidirectional"))
    )
    (net (code "41") (name "Net-(U$2-ENA{slash}DIAGA)") (class "Default")
      (node (ref "R4") (pin "1") (pinfunction "1_1") (pintype "passive"))
      (node (ref "R7") (pin "2") (pinfunction "2_2") (pintype "passive"))
      (node (ref "U$2") (pin "5") (pinfunction "ENA/DIAGA_5") (pintype "bidirectional"))
    )
    (net (code "42") (name "Net-(U$2-ENB{slash}DIAGB)") (class "Default")
      (node (ref "R3") (pin "1") (pinfunction "1_1") (pintype "passive"))
      (node (ref "R8") (pin "2") (pinfunction "2_2") (pintype "passive"))
      (node (ref "U$2") (pin "9") (pinfunction "ENB/DIAGB_9") (pintype "bidirectional"))
    )
    (net (code "43") (name "Net-(U$2-INA)") (class "Default")
      (node (ref "R5") (pin "1") (pinfunction "1_1") (pintype "passive"))
      (node (ref "U$2") (pin "4") (pinfunction "INA_4") (pintype "bidirectional"))
    )
    (net (code "44") (name "Net-(U$2-INB)") (class "Default")
      (node (ref "R6") (pin "1") (pinfunction "1_1") (pintype "passive"))
      (node (ref "U$2") (pin "10") (pinfunction "INB_10") (pintype "bidirectional"))
    )
    (net (code "45") (name "Net-(U$2-PWM)") (class "Default")
      (node (ref "R10") (pin "1") (pinfunction "1_1") (pintype "passive"))
      (node (ref "U$2") (pin "7") (pinfunction "PWM_7") (pintype "bidirectional"))
    )
    (net (code "46") (name "Net-(U$7-BOOT)") (class "Default")
      (node (ref "C14") (pin "1") (pinfunction "1_1") (pintype "passive"))
      (node (ref "U$7") (pin "1") (pinfunction "BOOT_1") (pintype "bidirectional"))
    )
    (net (code "47") (name "Net-(U$7-FB)") (class "Default")
      (node (ref "R13") (pin "1") (pinfunction "1_1") (pintype "passive"))
      (node (ref "R14") (pin "2") (pinfunction "2_2") (pintype "passive"))
      (node (ref "U$7") (pin "3") (pinfunction "FB_3") (pintype "bidirectional"))
    )
    (net (code "48") (name "Net-(U$7-PHASE)") (class "Default")
      (node (ref "C14") (pin "2") (pinfunction "2_2") (pintype "passive"))
      (node (ref "D1") (pin "C") (pinfunction "C_C") (pintype "passive"))
      (node (ref "U$7") (pin "6") (pinfunction "PHASE_6") (pintype "power_in"))
      (node (ref "U$8") (pin "1") (pinfunction "1_1") (pintype "passive"))
    )
    (net (code "49") (name "VCC") (class "Default")
      (node (ref "C20") (pin "1") (pinfunction "1_1") (pintype "passive"))
      (node (ref "C21") (pin "1") (pinfunction "1_1") (pintype "passive"))
      (node (ref "U$1") (pin "9") (pinfunction "VDD_A_9") (pintype "power_in"))
      (node (ref "U2") (pin "5") (pinfunction "OUT_5") (pintype "passive"))
    )
    (net (code "50") (name "VIN") (class "Default")
      (node (ref "U$2") (pin "12") (pinfunction "VBAT_12") (pintype "bidirectional"))
      (node (ref "U$4") (pin "3") (pinfunction "S_3") (pintype "bidirectional"))
      (node (ref "VIN") (pin "2") (pinfunction "2_2") (pintype "passive"))
    )
    (net (code "51") (name "VOUT") (class "Default")
      (node (ref "C11") (pin "1") (pinfunction "1_1") (pintype "passive"))
      (node (ref "C22") (pin "+") (pinfunction "+_+") (pintype "passive"))
      (node (ref "C23") (pin "+") (pinfunction "+_+") (pintype "passive"))
      (node (ref "C9") (pin "1") (pinfunction "1_1") (pintype "passive"))
      (node (ref "U$2") (pin "13") (pinfunction "VCC_13") (pintype "bidirectional"))
      (node (ref "U$2") (pin "23") (pinfunction "VCC_23") (pintype "bidirectional"))
      (node (ref "U$2") (pin "3") (pinfunction "VCC_3") (pintype "bidirectional"))
      (node (ref "U$2") (pin "VCC") (pinfunction "VCC_VCC") (pintype "bidirectional"))
      (node (ref "U$2") (pin "VCC@1") (pinfunction "VCC_VCC@1") (pintype "bidirectional"))
      (node (ref "U$4") (pin "2") (pinfunction "D_2") (pintype "bidirectional"))
      (node (ref "U$7") (pin "5") (pinfunction "VIN_5") (pintype "power_in"))
    )
    (net (code "52") (name "unconnected-(J-LINK-KEY-Pad7)") (class "Default")
      (node (ref "J-LINK") (pin "7") (pinfunction "KEY_7") (pintype "bidirectional"))
    )
    (net (code "53") (name "unconnected-(J-LINK-NC{slash}TDI-Pad8)") (class "Default")
      (node (ref "J-LINK") (pin "8") (pinfunction "NC/TDI_8") (pintype "bidirectional"))
    )
    (net (code "54") (name "unconnected-(J-LINK-SWO{slash}TDO-Pad6)") (class "Default")
      (node (ref "J-LINK") (pin "6") (pinfunction "SWO/TDO_6") (pintype "bidirectional"))
    )
    (net (code "55") (name "unconnected-(U$1-PA0_WKUP{slash}USART2_CTS{slash}ADC12_IN0{slash}TIM2_CH1_ETR-Pad10)") (class "Default")
      (node (ref "U$1") (pin "10") (pinfunction "PA0_WKUP/USART2_CTS/ADC12_IN0/TIM2_CH1_ETR_10") (pintype "bidirectional"))
    )
    (net (code "56") (name "unconnected-(U$1-PA1{slash}USART2_RTS{slash}ADC12_IN1{slash}TIM2_CH2-Pad11)") (class "Default")
      (node (ref "U$1") (pin "11") (pinfunction "PA1/USART2_RTS/ADC12_IN1/TIM2_CH2_11") (pintype "bidirectional"))
    )
    (net (code "57") (name "unconnected-(U$1-PA2{slash}USART2_TX{slash}ADC12_IN2{slash}TIM2_CH3-Pad12)") (class "Default")
      (node (ref "U$1") (pin "12") (pinfunction "PA2/USART2_TX/ADC12_IN2/TIM2_CH3_12") (pintype "bidirectional"))
    )
    (net (code "58") (name "unconnected-(U$1-PA3{slash}USART2_RX{slash}ADC12_IN3{slash}TIM2_CH4-Pad13)") (class "Default")
      (node (ref "U$1") (pin "13") (pinfunction "PA3/USART2_RX/ADC12_IN3/TIM2_CH4_13") (pintype "bidirectional"))
    )
    (net (code "59") (name "unconnected-(U$1-PA4{slash}SPI1_NSS{slash}USART2_CK{slash}ADC12_IN4-Pad14)") (class "Default")
      (node (ref "U$1") (pin "14") (pinfunction "PA4/SPI1_NSS/USART2_CK/ADC12_IN4_14") (pintype "bidirectional"))
    )
    (net (code "60") (name "unconnected-(U$1-PA5{slash}SPI1_SCK{slash}ADC12_IN5-Pad15)") (class "Default")
      (node (ref "U$1") (pin "15") (pinfunction "PA5/SPI1_SCK/ADC12_IN5_15") (pintype "bidirectional"))
    )
    (net (code "61") (name "unconnected-(U$1-PA6{slash}SPI1_MISO{slash}ADC12_IN6{slash}TIM3_CH1-Pad16)") (class "Default")
      (node (ref "U$1") (pin "16") (pinfunction "PA6/SPI1_MISO/ADC12_IN6/TIM3_CH1_16") (pintype "bidirectional"))
    )
    (net (code "62") (name "unconnected-(U$1-PA9{slash}USART1_TX{slash}TIM1_CH2-Pad30)") (class "Default")
      (node (ref "U$1") (pin "30") (pinfunction "PA9/USART1_TX/TIM1_CH2_30") (pintype "input"))
    )
    (net (code "63") (name "unconnected-(U$1-PA10{slash}USART1_RX{slash}TIM1_CH3-Pad31)") (class "Default")
      (node (ref "U$1") (pin "31") (pinfunction "PA10/USART1_RX/TIM1_CH3_31") (pintype "bidirectional"))
    )
    (net (code "64") (name "unconnected-(U$1-PA15{slash}JTDI-Pad38)") (class "Default")
      (node (ref "U$1") (pin "38") (pinfunction "PA15/JTDI_38") (pintype "bidirectional"))
    )
    (net (code "65") (name "unconnected-(U$1-PB8{slash}TIM4_CH3-Pad45)") (class "Default")
      (node (ref "U$1") (pin "45") (pinfunction "PB8/TIM4_CH3_45") (pintype "bidirectional"))
    )
    (net (code "66") (name "unconnected-(U$1-PB9{slash}TIM4_CH4-Pad46)") (class "Default")
      (node (ref "U$1") (pin "46") (pinfunction "PB9/TIM4_CH4_46") (pintype "input"))
    )
    (net (code "67") (name "unconnected-(U$1-PC13-TAMPER-RTC-Pad2)") (class "Default")
      (node (ref "U$1") (pin "2") (pinfunction "PC13-TAMPER-RTC_2") (pintype "input"))
    )
    (net (code "68") (name "unconnected-(U$1-PC14-OSC32_IN-Pad3)") (class "Default")
      (node (ref "U$1") (pin "3") (pinfunction "PC14-OSC32_IN_3") (pintype "input"))
    )
    (net (code "69") (name "unconnected-(U$1-PC15-OSC32_OUT-Pad4)") (class "Default")
      (node (ref "U$1") (pin "4") (pinfunction "PC15-OSC32_OUT_4") (pintype "input"))
    )
    (net (code "70") (name "unconnected-(U$2-CS_DIS-Pad6)") (class "Default")
      (node (ref "U$2") (pin "6") (pinfunction "CS_DIS_6") (pintype "bidirectional"))
    )
    (net (code "71") (name "unconnected-(U$7-EN-Pad4)") (class "Default")
      (node (ref "U$7") (pin "4") (pinfunction "EN_4") (pintype "bidirectional"))
    )
    (net (code "72") (name "unconnected-(U1-NC-Pad4)") (class "Default")
      (node (ref "U1") (pin "4") (pinfunction "NC_4") (pintype "no_connect"))
    )
    (net (code "73") (name "unconnected-(U2-NC-Pad4)") (class "Default")
      (node (ref "U2") (pin "4") (pinfunction "NC_4") (pintype "no_connect"))
    )
  )
)
